# lockitron-interface.net
KiCad netlist of a schematic drawn in EAGLE
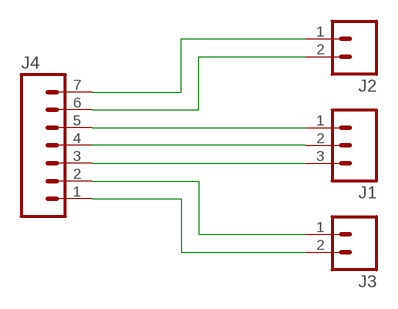
[diagram p0: schematic, sheet 1]

(export (version "E")
  (design (tool "Eeschema 10.0.6"))
  (components
    (comp (ref "J1")
      (value "M03SCREW")
      (footprint "eagle-import:SCREWTERMINAL-3.5MM-3")
      (libsource (lib "eagle-import") (part "M03SCREW"))
    )
    (comp (ref "J2")
      (value "M023.5MM")
      (footprint "eagle-import:SCREWTERMINAL-3.5MM-2")
      (libsource (lib "eagle-import") (part "M023.5MM"))
    )
    (comp (ref "J3")
      (value "M023.5MM")
      (footprint "eagle-import:SCREWTERMINAL-3.5MM-2")
      (libsource (lib "eagle-import") (part "M023.5MM"))
    )
    (comp (ref "J4")
      (value "M07LONGPADS")
      (footprint "eagle-import:1X07_LONGPADS")
      (libsource (lib "eagle-import") (part "M07LONGPADS"))
    )
  )
  (nets
    (net (code "1") (name "Net-(J1-Pad1)") (class "Default")
      (node (ref "J1") (pin "1") (pinfunction "1_1") (pintype "passive"))
      (node (ref "J4") (pin "5") (pinfunction "5_5") (pintype "passive"))
    )
    (net (code "2") (name "Net-(J1-Pad2)") (class "Default")
      (node (ref "J1") (pin "2") (pinfunction "2_2") (pintype "passive"))
      (node (ref "J4") (pin "4") (pinfunction "4_4") (pintype "passive"))
    )
    (net (code "3") (name "Net-(J1-Pad3)") (class "Default")
      (node (ref "J1") (pin "3") (pinfunction "3_3") (pintype "passive"))
      (node (ref "J4") (pin "3") (pinfunction "3_3") (pintype "passive"))
    )
    (net (code "4") (name "Net-(J2-Pad1)") (class "Default")
      (node (ref "J2") (pin "1") (pinfunction "1_1") (pintype "passive"))
      (node (ref "J4") (pin "7") (pinfunction "7_7") (pintype "passive"))
    )
    (net (code "5") (name "Net-(J2-Pad2)") (class "Default")
      (node (ref "J2") (pin "2") (pinfunction "2_2") (pintype "passive"))
      (node (ref "J4") (pin "6") (pinfunction "6_6") (pintype "passive"))
    )
    (net (code "6") (name "Net-(J3-Pad1)") (class "Default")
      (node (ref "J3") (pin "1") (pinfunction "1_1") (pintype "passive"))
      (node (ref "J4") (pin "2") (pinfunction "2_2") (pintype "passive"))
    )
    (net (code "7") (name "Net-(J3-Pad2)") (class "Default")
      (node (ref "J3") (pin "2") (pinfunction "2_2") (pintype "passive"))
      (node (ref "J4") (pin "1") (pinfunction "1_1") (pintype "passive"))
    )
  )
)
